# cutdownboard.net
KiCad netlist of a schematic drawn in EAGLE
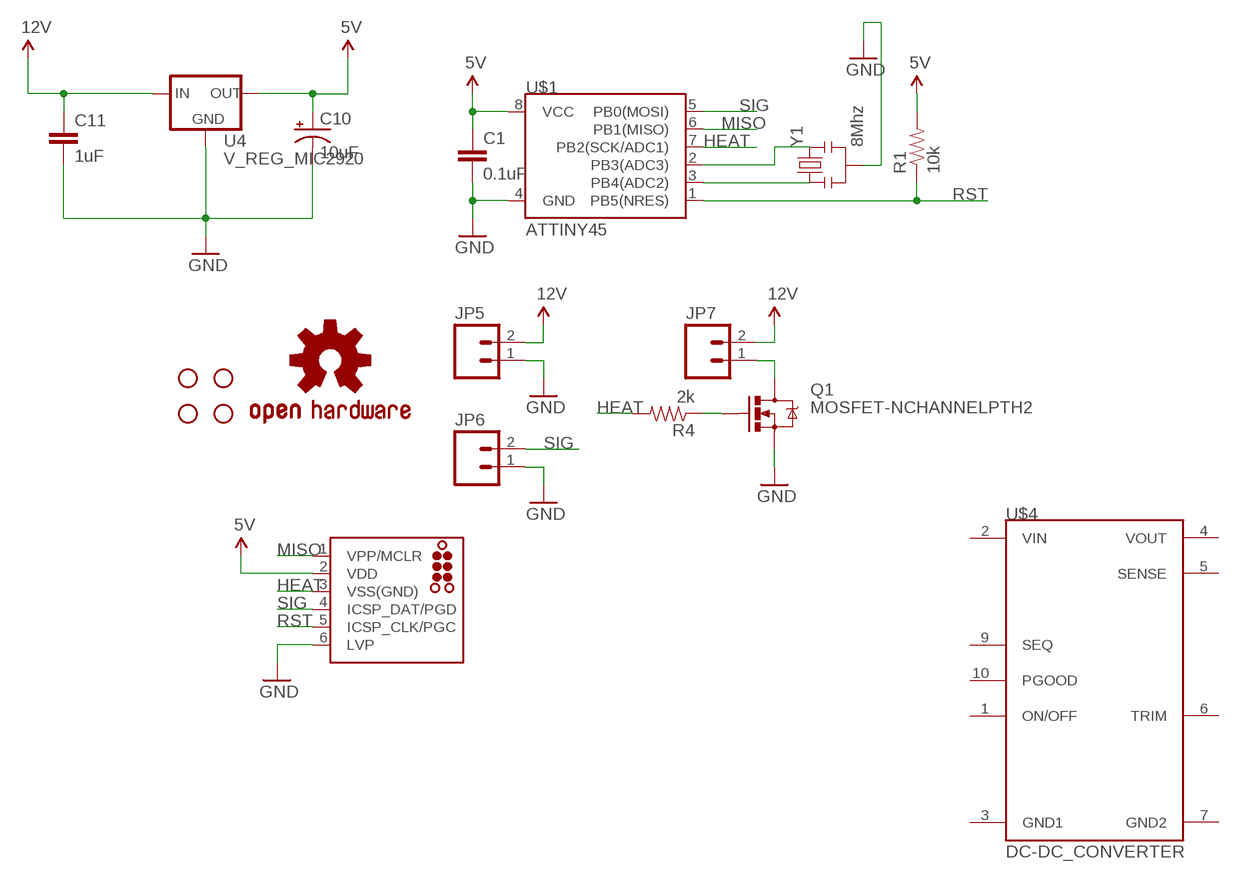
[diagram p0: schematic, sheet 1]

(export (version "E")
  (design (tool "Eeschema 10.0.6"))
  (components
    (comp (ref "C1")
      (value "0.1uF")
      (footprint "eagle-import:C0603")
      (libsource (lib "eagle-import") (part "C-EUC0603"))
    )
    (comp (ref "C10")
      (value "10uF")
      (footprint "eagle-import:EIA3216")
      (libsource (lib "eagle-import") (part "CAP_POL1206"))
    )
    (comp (ref "C11")
      (value "1uF")
      (footprint "eagle-import:C0603")
      (libsource (lib "eagle-import") (part "C-EUC0603"))
    )
    (comp (ref "J1")
      (value "TC2030-MCP")
      (footprint "eagle-import:TC2030-MCP")
      (libsource (lib "eagle-import") (part "TC2030-MCP"))
    )
    (comp (ref "JP1")
      (value "STAND-OFF")
      (footprint "eagle-import:STAND-OFF")
      (libsource (lib "eagle-import") (part "STAND-OFF"))
    )
    (comp (ref "JP2")
      (value "STAND-OFF")
      (footprint "eagle-import:STAND-OFF")
      (libsource (lib "eagle-import") (part "STAND-OFF"))
    )
    (comp (ref "JP3")
      (value "STAND-OFF")
      (footprint "eagle-import:STAND-OFF")
      (libsource (lib "eagle-import") (part "STAND-OFF"))
    )
    (comp (ref "JP4")
      (value "STAND-OFF")
      (footprint "eagle-import:STAND-OFF")
      (libsource (lib "eagle-import") (part "STAND-OFF"))
    )
    (comp (ref "JP5")
      (value "M02JST-PTH-2")
      (footprint "eagle-import:JST-2-PTH")
      (libsource (lib "eagle-import") (part "M02JST-PTH-2"))
    )
    (comp (ref "JP6")
      (value "M02JST-PTH-2")
      (footprint "eagle-import:JST-2-PTH")
      (libsource (lib "eagle-import") (part "M02JST-PTH-2"))
    )
    (comp (ref "JP7")
      (value "M02JST-PTH-2")
      (footprint "eagle-import:JST-2-PTH")
      (libsource (lib "eagle-import") (part "M02JST-PTH-2"))
    )
    (comp (ref "Q1")
      (value "MOSFET-NCHANNELPTH2")
      (footprint "eagle-import:TO220V")
      (libsource (lib "eagle-import") (part "MOSFET-NCHANNELPTH2"))
    )
    (comp (ref "R1")
      (value "10k")
      (footprint "eagle-import:0603-RES")
      (libsource (lib "eagle-import") (part "RESISTOR0603-RES"))
    )
    (comp (ref "R4")
      (value "2k")
      (footprint "eagle-import:0603-RES")
      (libsource (lib "eagle-import") (part "RESISTOR0603-RES"))
    )
    (comp (ref "U$1")
      (value "ATTINY45")
      (footprint "eagle-import:SO08-EIAJ")
      (libsource (lib "eagle-import") (part "ATTINY45"))
    )
    (comp (ref "U$4")
      (value "DC-DC_CONVERTER")
      (footprint "eagle-import:DC-DC_CONVERTER")
      (libsource (lib "eagle-import") (part "DC-DC_CONVERTER"))
    )
    (comp (ref "U$5")
      (value "OSHW-LOGOS")
      (footprint "eagle-import:OSHW-LOGO-S")
      (libsource (lib "eagle-import") (part "OSHW-LOGOS"))
    )
    (comp (ref "U4")
      (value "V_REG_MIC2920")
      (footprint "eagle-import:SOT223")
      (libsource (lib "eagle-import") (part "V_REG_MIC2920"))
    )
    (comp (ref "Y1")
      (value "8Mhz")
      (footprint "eagle-import:RESONATOR-SMD")
      (libsource (lib "eagle-import") (part "RESONATORSMD"))
    )
  )
  (nets
    (net (code "1") (name "/HEAT") (class "Default")
      (node (ref "J1") (pin "3") (pinfunction "VSS(GND)_3") (pintype "power_in"))
      (node (ref "R4") (pin "2") (pinfunction "2_2") (pintype "passive"))
      (node (ref "U$1") (pin "7") (pinfunction "PB2(SCK/ADC1)_7") (pintype "bidirectional"))
    )
    (net (code "2") (name "/MISO") (class "Default")
      (node (ref "J1") (pin "1") (pinfunction "VPP/MCLR_1") (pintype "passive"))
      (node (ref "U$1") (pin "6") (pinfunction "PB1(MISO)_6") (pintype "bidirectional"))
    )
    (net (code "3") (name "/RST") (class "Default")
      (node (ref "J1") (pin "5") (pinfunction "ICSP_CLK/PGC_5") (pintype "output"))
      (node (ref "R1") (pin "1") (pinfunction "1_1") (pintype "passive"))
      (node (ref "U$1") (pin "1") (pinfunction "PB5(NRES)_1") (pintype "bidirectional"))
    )
    (net (code "4") (name "/SIG") (class "Default")
      (node (ref "J1") (pin "4") (pinfunction "ICSP_DAT/PGD_4") (pintype "bidirectional"))
      (node (ref "JP6") (pin "2") (pinfunction "2_2") (pintype "passive"))
      (node (ref "U$1") (pin "5") (pinfunction "PB0(MOSI)_5") (pintype "bidirectional"))
    )
    (net (code "5") (name "5V") (class "Default")
      (node (ref "C1") (pin "1") (pinfunction "1_1") (pintype "passive"))
      (node (ref "C10") (pin "A") (pinfunction "+_A") (pintype "passive"))
      (node (ref "J1") (pin "2") (pinfunction "VDD_2") (pintype "power_in"))
      (node (ref "R1") (pin "2") (pinfunction "2_2") (pintype "passive"))
      (node (ref "U$1") (pin "8") (pinfunction "VCC_8") (pintype "bidirectional"))
      (node (ref "U4") (pin "3") (pinfunction "OUT_3") (pintype "output"))
    )
    (net (code "6") (name "12V") (class "Default")
      (node (ref "C11") (pin "1") (pinfunction "1_1") (pintype "passive"))
      (node (ref "JP5") (pin "2") (pinfunction "2_2") (pintype "passive"))
      (node (ref "JP7") (pin "2") (pinfunction "2_2") (pintype "passive"))
      (node (ref "U4") (pin "1") (pinfunction "IN_1") (pintype "input"))
    )
    (net (code "7") (name "GND") (class "Default")
      (node (ref "C1") (pin "2") (pinfunction "2_2") (pintype "passive"))
      (node (ref "C10") (pin "C") (pinfunction "-_C") (pintype "passive"))
      (node (ref "C11") (pin "2") (pinfunction "2_2") (pintype "passive"))
      (node (ref "J1") (pin "6") (pinfunction "LVP_6") (pintype "bidirectional"))
      (node (ref "JP5") (pin "1") (pinfunction "1_1") (pintype "passive"))
      (node (ref "JP6") (pin "1") (pinfunction "1_1") (pintype "passive"))
      (node (ref "Q1") (pin "3") (pinfunction "S_3") (pintype "passive"))
      (node (ref "U$1") (pin "4") (pinfunction "GND_4") (pintype "bidirectional"))
      (node (ref "U4") (pin "2") (pinfunction "GND_2") (pintype "input"))
      (node (ref "Y1") (pin "2") (pinfunction "2_2") (pintype "passive"))
    )
    (net (code "8") (name "Net-(Q1-D)") (class "Default")
      (node (ref "JP7") (pin "1") (pinfunction "1_1") (pintype "passive"))
      (node (ref "Q1") (pin "2") (pinfunction "D_2") (pintype "passive"))
    )
    (net (code "9") (name "Net-(Q1-G)") (class "Default")
      (node (ref "Q1") (pin "1") (pinfunction "G_1") (pintype "passive"))
      (node (ref "R4") (pin "1") (pinfunction "1_1") (pintype "passive"))
    )
    (net (code "10") (name "Net-(U$1-PB3(ADC3))") (class "Default")
      (node (ref "U$1") (pin "2") (pinfunction "PB3(ADC3)_2") (pintype "bidirectional"))
      (node (ref "Y1") (pin "3") (pinfunction "3_3") (pintype "passive"))
    )
    (net (code "11") (name "Net-(U$1-PB4(ADC2))") (class "Default")
      (node (ref "U$1") (pin "3") (pinfunction "PB4(ADC2)_3") (pintype "bidirectional"))
      (node (ref "Y1") (pin "1") (pinfunction "1_1") (pintype "passive"))
    )
    (net (code "12") (name "unconnected-(U$4-GND1-Pad3)") (class "Default")
      (node (ref "U$4") (pin "3") (pinfunction "GND1_3") (pintype "bidirectional"))
    )
    (net (code "13") (name "unconnected-(U$4-GND2-Pad7)") (class "Default")
      (node (ref "U$4") (pin "7") (pinfunction "GND2_7") (pintype "bidirectional"))
    )
    (net (code "14") (name "unconnected-(U$4-ON{slash}OFF-Pad1)") (class "Default")
      (node (ref "U$4") (pin "1") (pinfunction "ON/OFF_1") (pintype "bidirectional"))
    )
    (net (code "15") (name "unconnected-(U$4-PGOOD-Pad10)") (class "Default")
      (node (ref "U$4") (pin "10") (pinfunction "PGOOD_10") (pintype "bidirectional"))
    )
    (net (code "16") (name "unconnected-(U$4-SENSE-Pad5)") (class "Default")
      (node (ref "U$4") (pin "5") (pinfunction "SENSE_5") (pintype "bidirectional"))
    )
    (net (code "17") (name "unconnected-(U$4-SEQ-Pad9)") (class "Default")
      (node (ref "U$4") (pin "9") (pinfunction "SEQ_9") (pintype "bidirectional"))
    )
    (net (code "18") (name "unconnected-(U$4-TRIM-Pad6)") (class "Default")
      (node (ref "U$4") (pin "6") (pinfunction "TRIM_6") (pintype "bidirectional"))
    )
    (net (code "19") (name "unconnected-(U$4-VIN-Pad2)") (class "Default")
      (node (ref "U$4") (pin "2") (pinfunction "VIN_2") (pintype "bidirectional"))
    )
    (net (code "20") (name "unconnected-(U$4-VOUT-Pad4)") (class "Default")
      (node (ref "U$4") (pin "4") (pinfunction "VOUT_4") (pintype "bidirectional"))
    )
  )
)
